# Parallel_CS_V5.net
KiCad netlist of a schematic drawn in EAGLE
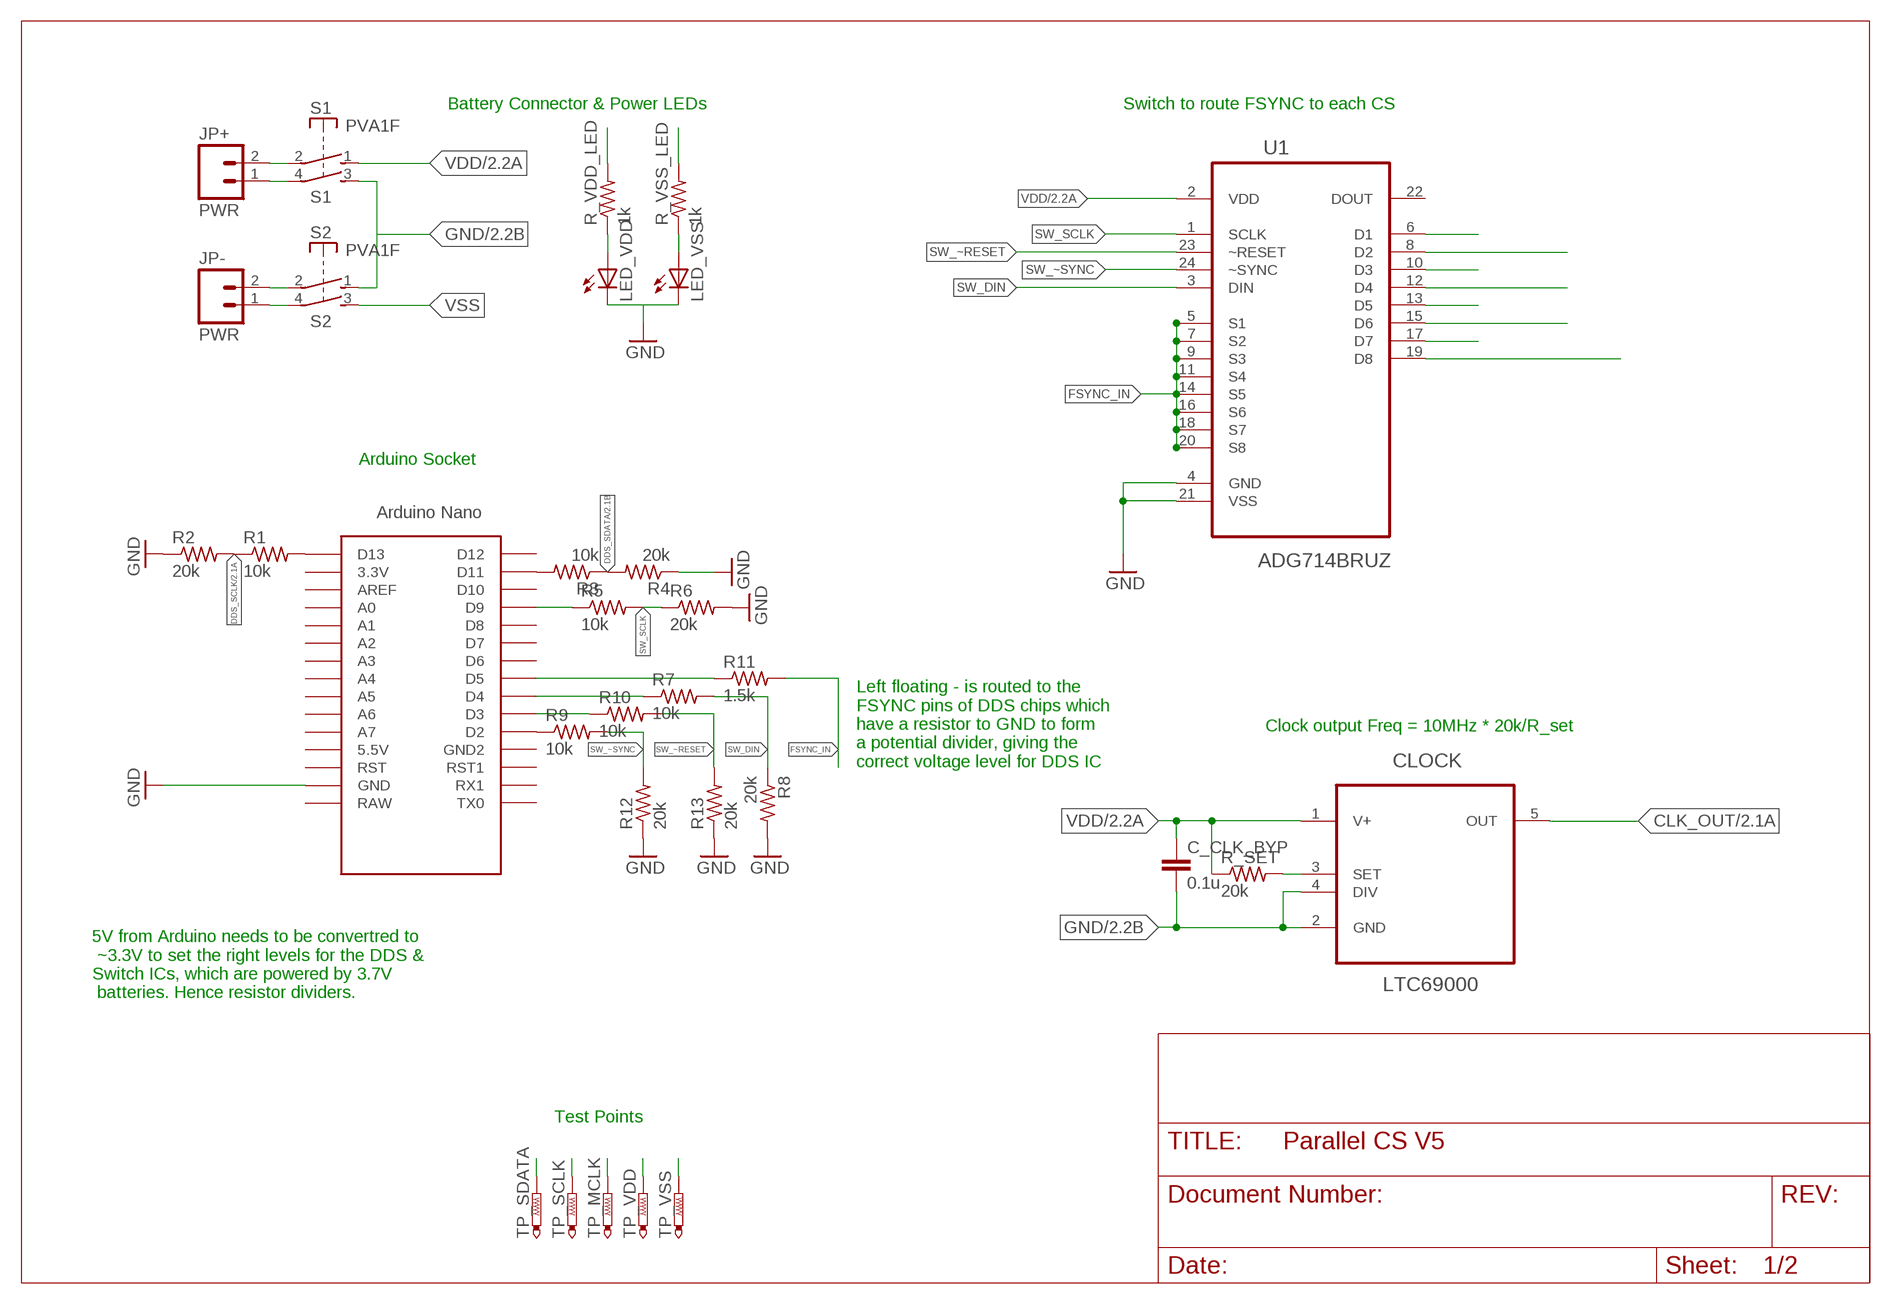
[diagram p0: schematic, sheet 1]
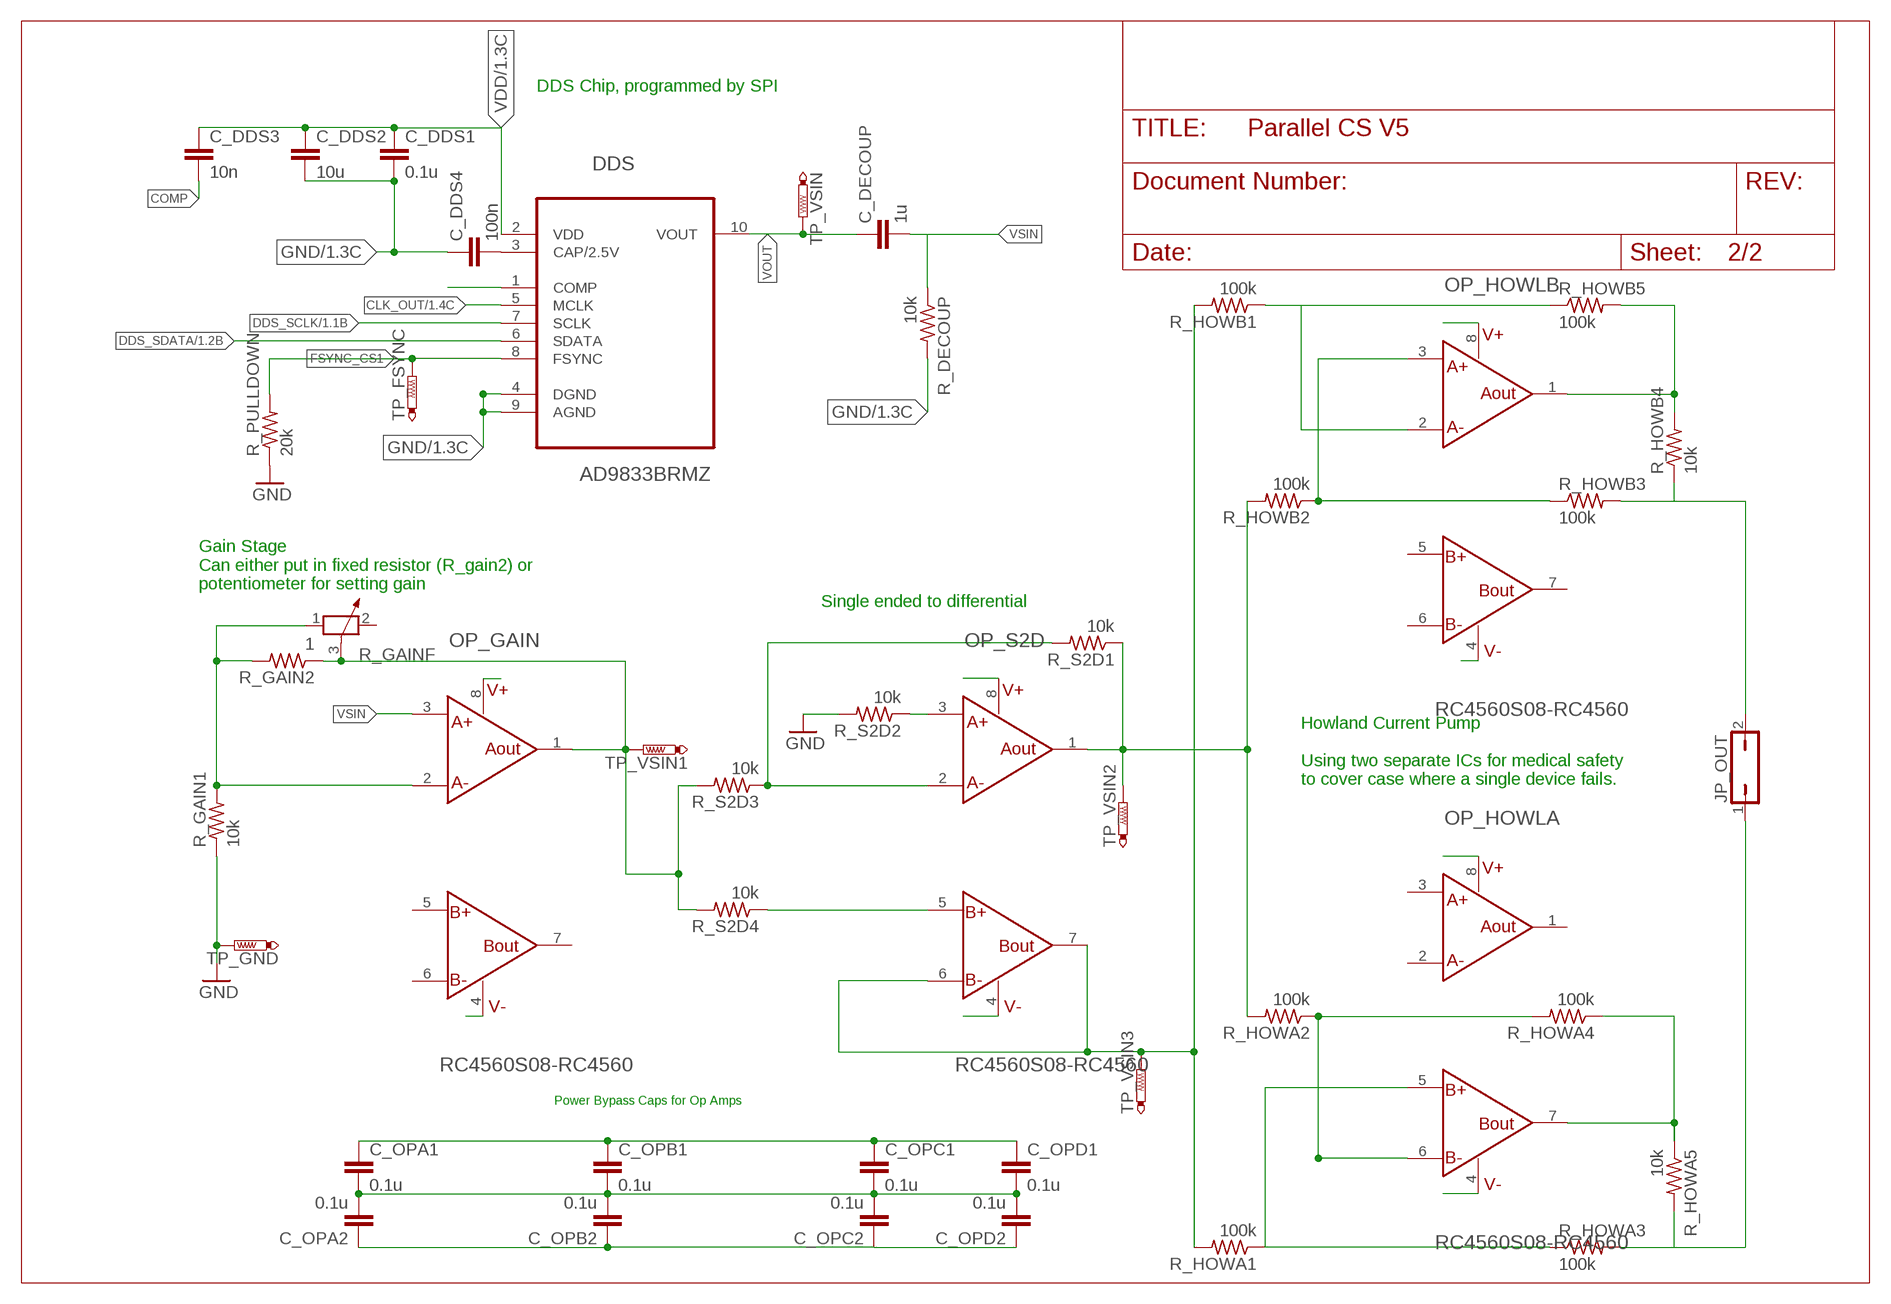
[diagram p1: schematic, sheet 2]

(export (version "E")
  (design (tool "Eeschema 10.0.6"))
  (components
    (comp (ref "CLOCK")
      (value "LTC69000")
      (footprint "eagle-import:SOT23-5L")
      (libsource (lib "eagle-import") (part "LTC69000"))
    )
    (comp (ref "C_CLK_BYP")
      (value "0.1u")
      (footprint "eagle-import:C0805")
      (libsource (lib "eagle-import") (part "C-EUC0805"))
    )
    (comp (ref "JP+")
      (value "PWR")
      (footprint "eagle-import:JST-2-SMD")
      (libsource (lib "eagle-import") (part "M02-JST-2MM-SMT"))
    )
    (comp (ref "JP-")
      (value "PWR")
      (footprint "eagle-import:JST-2-SMD")
      (libsource (lib "eagle-import") (part "M02-JST-2MM-SMT"))
    )
    (comp (ref "LED_VDD")
      (value "LEDSML0805")
      (footprint "eagle-import:SML0805")
      (libsource (lib "eagle-import") (part "LEDSML0805"))
    )
    (comp (ref "LED_VSS")
      (value "LEDSML0805")
      (footprint "eagle-import:SML0805")
      (libsource (lib "eagle-import") (part "LEDSML0805"))
    )
    (comp (ref "R1")
      (value "10k")
      (footprint "eagle-import:R0805")
      (libsource (lib "eagle-import") (part "resistor_R-US_R0805"))
    )
    (comp (ref "R2")
      (value "20k")
      (footprint "eagle-import:R0805")
      (libsource (lib "eagle-import") (part "resistor_R-US_R0805"))
    )
    (comp (ref "R3")
      (value "10k")
      (footprint "eagle-import:R0805")
      (libsource (lib "eagle-import") (part "resistor_R-US_R0805"))
    )
    (comp (ref "R4")
      (value "20k")
      (footprint "eagle-import:R0805")
      (libsource (lib "eagle-import") (part "resistor_R-US_R0805"))
    )
    (comp (ref "R5")
      (value "10k")
      (footprint "eagle-import:R0805")
      (libsource (lib "eagle-import") (part "resistor_R-US_R0805"))
    )
    (comp (ref "R6")
      (value "20k")
      (footprint "eagle-import:R0805")
      (libsource (lib "eagle-import") (part "resistor_R-US_R0805"))
    )
    (comp (ref "R7")
      (value "10k")
      (footprint "eagle-import:R0805")
      (libsource (lib "eagle-import") (part "resistor_R-US_R0805"))
    )
    (comp (ref "R8")
      (value "20k")
      (footprint "eagle-import:R0805")
      (libsource (lib "eagle-import") (part "resistor_R-US_R0805"))
    )
    (comp (ref "R9")
      (value "10k")
      (footprint "eagle-import:R0805")
      (libsource (lib "eagle-import") (part "resistor_R-US_R0805"))
    )
    (comp (ref "R10")
      (value "10k")
      (footprint "eagle-import:R0805")
      (libsource (lib "eagle-import") (part "resistor_R-US_R0805"))
    )
    (comp (ref "R11")
      (value "1.5k")
      (footprint "eagle-import:R0805")
      (libsource (lib "eagle-import") (part "resistor_R-US_R0805"))
    )
    (comp (ref "R12")
      (value "20k")
      (footprint "eagle-import:R0805")
      (libsource (lib "eagle-import") (part "resistor_R-US_R0805"))
    )
    (comp (ref "R13")
      (value "20k")
      (footprint "eagle-import:R0805")
      (libsource (lib "eagle-import") (part "resistor_R-US_R0805"))
    )
    (comp (ref "R_SET")
      (value "20k")
      (footprint "eagle-import:R0805")
      (libsource (lib "eagle-import") (part "resistor_R-US_R0805"))
    )
    (comp (ref "R_VDD_LED")
      (value "1k")
      (footprint "eagle-import:M0805")
      (libsource (lib "eagle-import") (part "resistor_R-US_M0805"))
    )
    (comp (ref "R_VSS_LED")
      (value "1k")
      (footprint "eagle-import:M0805")
      (libsource (lib "eagle-import") (part "resistor_R-US_M0805"))
    )
    (comp (ref "S1")
      (value "PVA1F")
      (footprint "eagle-import:PVA1F")
      (libsource (lib "eagle-import") (part "PVA1F"))
    )
    (comp (ref "S2")
      (value "PVA1F")
      (footprint "eagle-import:PVA1F")
      (libsource (lib "eagle-import") (part "PVA1F"))
    )
    (comp (ref "TP_MCLK")
      (value "PTR1PAD1-13")
      (footprint "eagle-import:P1-13")
      (libsource (lib "eagle-import") (part "PTR1PAD1-13"))
    )
    (comp (ref "TP_SCLK")
      (value "PTR1PAD1-13")
      (footprint "eagle-import:P1-13")
      (libsource (lib "eagle-import") (part "PTR1PAD1-13"))
    )
    (comp (ref "TP_SDATA")
      (value "PTR1PAD1-13")
      (footprint "eagle-import:P1-13")
      (libsource (lib "eagle-import") (part "PTR1PAD1-13"))
    )
    (comp (ref "TP_VDD")
      (value "PTR1PAD1-13")
      (footprint "eagle-import:P1-13")
      (libsource (lib "eagle-import") (part "PTR1PAD1-13"))
    )
    (comp (ref "TP_VSS")
      (value "PTR1PAD1-13")
      (footprint "eagle-import:P1-13")
      (libsource (lib "eagle-import") (part "PTR1PAD1-13"))
    )
    (comp (ref "U$1")
      (value "NANO")
      (footprint "eagle-import:NANO")
      (libsource (lib "eagle-import") (part "NANO"))
    )
    (comp (ref "U1")
      (value "ADG714BRUZ")
      (footprint "eagle-import:SOP65P640X120-24N")
      (libsource (lib "eagle-import") (part "ADG714BRUZ"))
    )
    (comp (ref "C_DDS1")
      (value "0.1u")
      (footprint "eagle-import:C0805")
      (libsource (lib "eagle-import") (part "C-EUC0805"))
    )
    (comp (ref "C_DDS2")
      (value "10u")
      (footprint "eagle-import:C0805")
      (libsource (lib "eagle-import") (part "C-EUC0805"))
    )
    (comp (ref "C_DDS3")
      (value "10n")
      (footprint "eagle-import:C0805")
      (libsource (lib "eagle-import") (part "C-EUC0805"))
    )
    (comp (ref "C_DDS4")
      (value "100n")
      (footprint "eagle-import:C0805")
      (libsource (lib "eagle-import") (part "C-EUC0805"))
    )
    (comp (ref "C_DECOUP")
      (value "1u")
      (footprint "eagle-import:C0805")
      (libsource (lib "eagle-import") (part "C-EUC0805"))
    )
    (comp (ref "C_OPA1")
      (value "0.1u")
      (footprint "eagle-import:C0805")
      (libsource (lib "eagle-import") (part "C-EUC0805"))
    )
    (comp (ref "C_OPA2")
      (value "0.1u")
      (footprint "eagle-import:C0805")
      (libsource (lib "eagle-import") (part "C-EUC0805"))
    )
    (comp (ref "C_OPB1")
      (value "0.1u")
      (footprint "eagle-import:C0805")
      (libsource (lib "eagle-import") (part "C-EUC0805"))
    )
    (comp (ref "C_OPB2")
      (value "0.1u")
      (footprint "eagle-import:C0805")
      (libsource (lib "eagle-import") (part "C-EUC0805"))
    )
    (comp (ref "C_OPC1")
      (value "0.1u")
      (footprint "eagle-import:C0805")
      (libsource (lib "eagle-import") (part "C-EUC0805"))
    )
    (comp (ref "C_OPC2")
      (value "0.1u")
      (footprint "eagle-import:C0805")
      (libsource (lib "eagle-import") (part "C-EUC0805"))
    )
    (comp (ref "C_OPD1")
      (value "0.1u")
      (footprint "eagle-import:C0805")
      (libsource (lib "eagle-import") (part "C-EUC0805"))
    )
    (comp (ref "C_OPD2")
      (value "0.1u")
      (footprint "eagle-import:C0805")
      (libsource (lib "eagle-import") (part "C-EUC0805"))
    )
    (comp (ref "DDS")
      (value "AD9833BRMZ")
      (footprint "eagle-import:SOP50P490X110-10N")
      (libsource (lib "eagle-import") (part "AD9833BRMZ"))
    )
    (comp (ref "JP_OUT")
      (value "JP1Q")
      (footprint "eagle-import:JP1")
      (libsource (lib "eagle-import") (part "JP1Q"))
    )
    (comp (ref "OP_GAIN")
      (value "RC4560S08-RC4560")
      (footprint "eagle-import:SO8")
      (libsource (lib "eagle-import") (part "RC4560S08-RC4560"))
    )
    (comp (ref "OP_HOWLA")
      (value "RC4560S08-RC4560")
      (footprint "eagle-import:SO8")
      (libsource (lib "eagle-import") (part "RC4560S08-RC4560"))
    )
    (comp (ref "OP_HOWLB")
      (value "RC4560S08-RC4560")
      (footprint "eagle-import:SO8")
      (libsource (lib "eagle-import") (part "RC4560S08-RC4560"))
    )
    (comp (ref "OP_S2D")
      (value "RC4560S08-RC4560")
      (footprint "eagle-import:SO8")
      (libsource (lib "eagle-import") (part "RC4560S08-RC4560"))
    )
    (comp (ref "R_DECOUP")
      (value "10k")
      (footprint "eagle-import:R0805")
      (libsource (lib "eagle-import") (part "R-US_R0805"))
    )
    (comp (ref "R_GAIN1")
      (value "10k")
      (footprint "eagle-import:R0805")
      (libsource (lib "eagle-import") (part "R-US_R0805"))
    )
    (comp (ref "R_GAIN2")
      (value "1")
      (footprint "eagle-import:R0805")
      (libsource (lib "eagle-import") (part "R-US_R0805"))
    )
    (comp (ref "R_GAINF")
      (value "POTENTIOMETER_PT-10")
      (footprint "eagle-import:PT-10")
      (libsource (lib "eagle-import") (part "POTENTIOMETER_PT-10"))
    )
    (comp (ref "R_HOWA1")
      (value "100k")
      (footprint "eagle-import:R0805")
      (libsource (lib "eagle-import") (part "R-US_R0805"))
    )
    (comp (ref "R_HOWA2")
      (value "100k")
      (footprint "eagle-import:R0805")
      (libsource (lib "eagle-import") (part "R-US_R0805"))
    )
    (comp (ref "R_HOWA3")
      (value "100k")
      (footprint "eagle-import:R0805")
      (libsource (lib "eagle-import") (part "R-US_R0805"))
    )
    (comp (ref "R_HOWA4")
      (value "100k")
      (footprint "eagle-import:R0805")
      (libsource (lib "eagle-import") (part "R-US_R0805"))
    )
    (comp (ref "R_HOWA5")
      (value "10k")
      (footprint "eagle-import:R0805")
      (libsource (lib "eagle-import") (part "R-US_R0805"))
    )
    (comp (ref "R_HOWB1")
      (value "100k")
      (footprint "eagle-import:R0805")
      (libsource (lib "eagle-import") (part "R-US_R0805"))
    )
    (comp (ref "R_HOWB2")
      (value "100k")
      (footprint "eagle-import:R0805")
      (libsource (lib "eagle-import") (part "R-US_R0805"))
    )
    (comp (ref "R_HOWB3")
      (value "100k")
      (footprint "eagle-import:R0805")
      (libsource (lib "eagle-import") (part "R-US_R0805"))
    )
    (comp (ref "R_HOWB4")
      (value "10k")
      (footprint "eagle-import:R0805")
      (libsource (lib "eagle-import") (part "R-US_R0805"))
    )
    (comp (ref "R_HOWB5")
      (value "100k")
      (footprint "eagle-import:R0805")
      (libsource (lib "eagle-import") (part "R-US_R0805"))
    )
    (comp (ref "R_PULLDOWN")
      (value "20k")
      (footprint "eagle-import:R0805")
      (libsource (lib "eagle-import") (part "R-US_R0805"))
    )
    (comp (ref "R_S2D1")
      (value "10k")
      (footprint "eagle-import:R0805")
      (libsource (lib "eagle-import") (part "R-US_R0805"))
    )
    (comp (ref "R_S2D2")
      (value "10k")
      (footprint "eagle-import:R0805")
      (libsource (lib "eagle-import") (part "R-US_R0805"))
    )
    (comp (ref "R_S2D3")
      (value "10k")
      (footprint "eagle-import:R0805")
      (libsource (lib "eagle-import") (part "R-US_R0805"))
    )
    (comp (ref "R_S2D4")
      (value "10k")
      (footprint "eagle-import:R0805")
      (libsource (lib "eagle-import") (part "R-US_R0805"))
    )
    (comp (ref "TP_FSYNC")
      (value "PTR1PAD1-13")
      (footprint "eagle-import:P1-13")
      (libsource (lib "eagle-import") (part "PTR1PAD1-13"))
    )
    (comp (ref "TP_GND")
      (value "PTR1PAD1-13")
      (footprint "eagle-import:P1-13")
      (libsource (lib "eagle-import") (part "PTR1PAD1-13"))
    )
    (comp (ref "TP_VSIN")
      (value "PTR1PAD1-13")
      (footprint "eagle-import:P1-13")
      (libsource (lib "eagle-import") (part "PTR1PAD1-13"))
    )
    (comp (ref "TP_VSIN1")
      (value "PTR1PAD1-13")
      (footprint "eagle-import:P1-13")
      (libsource (lib "eagle-import") (part "PTR1PAD1-13"))
    )
    (comp (ref "TP_VSIN2")
      (value "PTR1PAD1-13")
      (footprint "eagle-import:P1-13")
      (libsource (lib "eagle-import") (part "PTR1PAD1-13"))
    )
    (comp (ref "TP_VSIN3")
      (value "PTR1PAD1-13")
      (footprint "eagle-import:P1-13")
      (libsource (lib "eagle-import") (part "PTR1PAD1-13"))
    )
  )
  (nets
    (net (code "1") (name "CLK_OUT") (class "Default")
      (node (ref "CLOCK") (pin "5") (pinfunction "OUT_5") (pintype "output"))
      (node (ref "DDS") (pin "5") (pinfunction "MCLK_5") (pintype "input"))
      (node (ref "TP_MCLK") (pin "TP") (pinfunction "TP_TP") (pintype "input"))
    )
    (net (code "2") (name "COMP") (class "Default")
      (node (ref "C_DDS3") (pin "2") (pinfunction "2_2") (pintype "passive"))
      (node (ref "DDS") (pin "1") (pinfunction "COMP_1") (pintype "passive"))
    )
    (net (code "3") (name "DDS_SCLK") (class "Default")
      (node (ref "DDS") (pin "7") (pinfunction "SCLK_7") (pintype "input"))
      (node (ref "R1") (pin "1") (pinfunction "1_1") (pintype "passive"))
      (node (ref "R2") (pin "2") (pinfunction "2_2") (pintype "passive"))
      (node (ref "TP_SCLK") (pin "TP") (pinfunction "TP_TP") (pintype "input"))
    )
    (net (code "4") (name "DDS_SDATA") (class "Default")
      (node (ref "DDS") (pin "6") (pinfunction "SDATA_6") (pintype "input"))
      (node (ref "R3") (pin "1") (pinfunction "1_1") (pintype "passive"))
      (node (ref "R4") (pin "2") (pinfunction "2_2") (pintype "passive"))
      (node (ref "TP_SDATA") (pin "TP") (pinfunction "TP_TP") (pintype "input"))
    )
    (net (code "5") (name "FSYNC_CS1") (class "Default")
      (node (ref "DDS") (pin "8") (pinfunction "FSYNC_8") (pintype "input"))
      (node (ref "R_PULLDOWN") (pin "2") (pinfunction "2_2") (pintype "passive"))
      (node (ref "TP_FSYNC") (pin "TP") (pinfunction "TP_TP") (pintype "input"))
      (node (ref "U1") (pin "6") (pinfunction "D1_6") (pintype "bidirectional"))
    )
    (net (code "6") (name "FSYNC_IN") (class "Default")
      (node (ref "R11") (pin "2") (pinfunction "2_2") (pintype "passive"))
      (node (ref "U1") (pin "11") (pinfunction "S4_11") (pintype "bidirectional"))
      (node (ref "U1") (pin "14") (pinfunction "S5_14") (pintype "bidirectional"))
      (node (ref "U1") (pin "16") (pinfunction "S6_16") (pintype "bidirectional"))
      (node (ref "U1") (pin "18") (pinfunction "S7_18") (pintype "bidirectional"))
      (node (ref "U1") (pin "20") (pinfunction "S8_20") (pintype "bidirectional"))
      (node (ref "U1") (pin "5") (pinfunction "S1_5") (pintype "bidirectional"))
      (node (ref "U1") (pin "7") (pinfunction "S2_7") (pintype "bidirectional"))
      (node (ref "U1") (pin "9") (pinfunction "S3_9") (pintype "bidirectional"))
    )
    (net (code "7") (name "GND") (class "Default")
      (node (ref "CLOCK") (pin "2") (pinfunction "GND_2") (pintype "passive"))
      (node (ref "CLOCK") (pin "4") (pinfunction "DIV_4") (pintype "input"))
      (node (ref "C_CLK_BYP") (pin "2") (pinfunction "2_2") (pintype "passive"))
      (node (ref "C_DDS1") (pin "2") (pinfunction "2_2") (pintype "passive"))
      (node (ref "C_DDS2") (pin "2") (pinfunction "2_2") (pintype "passive"))
      (node (ref "C_DDS4") (pin "1") (pinfunction "1_1") (pintype "passive"))
      (node (ref "C_OPA1") (pin "2") (pinfunction "2_2") (pintype "passive"))
      (node (ref "C_OPA2") (pin "2") (pinfunction "2_2") (pintype "passive"))
      (node (ref "C_OPB1") (pin "2") (pinfunction "2_2") (pintype "passive"))
      (node (ref "C_OPB2") (pin "2") (pinfunction "2_2") (pintype "passive"))
      (node (ref "C_OPC1") (pin "2") (pinfunction "2_2") (pintype "passive"))
      (node (ref "C_OPC2") (pin "2") (pinfunction "2_2") (pintype "passive"))
      (node (ref "C_OPD1") (pin "2") (pinfunction "2_2") (pintype "passive"))
      (node (ref "C_OPD2") (pin "2") (pinfunction "2_2") (pintype "passive"))
      (node (ref "DDS") (pin "4") (pinfunction "DGND_4") (pintype "passive"))
      (node (ref "DDS") (pin "9") (pinfunction "AGND_9") (pintype "passive"))
      (node (ref "LED_VDD") (pin "C") (pinfunction "C_C") (pintype "passive"))
      (node (ref "LED_VSS") (pin "C") (pinfunction "C_C") (pintype "passive"))
      (node (ref "R12") (pin "1") (pinfunction "1_1") (pintype "passive"))
      (node (ref "R13") (pin "1") (pinfunction "1_1") (pintype "passive"))
      (node (ref "R2") (pin "1") (pinfunction "1_1") (pintype "passive"))
      (node (ref "R4") (pin "1") (pinfunction "1_1") (pintype "passive"))
      (node (ref "R6") (pin "2") (pinfunction "2_2") (pintype "passive"))
      (node (ref "R8") (pin "2") (pinfunction "2_2") (pintype "passive"))
      (node (ref "R_DECOUP") (pin "2") (pinfunction "2_2") (pintype "passive"))
      (node (ref "R_GAIN1") (pin "1") (pinfunction "1_1") (pintype "passive"))
      (node (ref "R_PULLDOWN") (pin "1") (pinfunction "1_1") (pintype "passive"))
      (node (ref "R_S2D2") (pin "2") (pinfunction "2_2") (pintype "passive"))
      (node (ref "S1") (pin "3") (pinfunction "S_3") (pintype "passive"))
      (node (ref "S2") (pin "1") (pinfunction "S_1") (pintype "passive"))
      (node (ref "TP_GND") (pin "TP") (pinfunction "TP_TP") (pintype "input"))
      (node (ref "U$1") (pin "GND") (pinfunction "GND_GND") (pintype "bidirectional"))
      (node (ref "U1") (pin "21") (pinfunction "VSS_21") (pintype "power_in"))
      (node (ref "U1") (pin "4") (pinfunction "GND_4") (pintype "passive"))
    )
    (net (code "8") (name "Net-(CLOCK-SET)") (class "Default")
      (node (ref "CLOCK") (pin "3") (pinfunction "SET_3") (pintype "input"))
      (node (ref "R_SET") (pin "2") (pinfunction "2_2") (pintype "passive"))
    )
    (net (code "9") (name "Net-(DDS-CAP{slash}2.5V)") (class "Default")
      (node (ref "C_DDS4") (pin "2") (pinfunction "2_2") (pintype "passive"))
      (node (ref "DDS") (pin "3") (pinfunction "CAP/2.5V_3") (pintype "passive"))
    )
    (net (code "10") (name "Net-(JP_OUT-Pad1)") (class "Default")
      (node (ref "JP_OUT") (pin "1") (pinfunction "1_1") (pintype "passive"))
      (node (ref "R_HOWA3") (pin "2") (pinfunction "2_2") (pintype "passive"))
      (node (ref "R_HOWA5") (pin "2") (pinfunction "2_2") (pintype "passive"))
    )
    (net (code "11") (name "Net-(JP_OUT-Pad2)") (class "Default")
      (node (ref "JP_OUT") (pin "2") (pinfunction "2_2") (pintype "passive"))
      (node (ref "R_HOWB3") (pin "2") (pinfunction "2_2") (pintype "passive"))
      (node (ref "R_HOWB4") (pin "1") (pinfunction "1_1") (pintype "passive"))
    )
    (net (code "12") (name "Net-(LED_VDD-PadA)") (class "Default")
      (node (ref "LED_VDD") (pin "A") (pinfunction "A_A") (pintype "passive"))
      (node (ref "R_VDD_LED") (pin "1") (pinfunction "1_1") (pintype "passive"))
    )
    (net (code "13") (name "Net-(LED_VSS-PadA)") (class "Default")
      (node (ref "LED_VSS") (pin "A") (pinfunction "A_A") (pintype "passive"))
      (node (ref "R_VSS_LED") (pin "1") (pinfunction "1_1") (pintype "passive"))
    )
    (net (code "14") (name "Net-(OP_GAIN-NEGA)") (class "Default")
      (node (ref "OP_GAIN") (pin "2") (pinfunction "NEGA_2") (pintype "input"))
      (node (ref "R_GAIN1") (pin "2") (pinfunction "2_2") (pintype "passive"))
      (node (ref "R_GAIN2") (pin "2") (pinfunction "2_2") (pintype "passive"))
      (node (ref "R_GAINF") (pin "1") (pinfunction "1_1") (pintype "passive"))
    )
    (net (code "15") (name "Net-(OP_GAIN-OUTA)") (class "Default")
      (node (ref "OP_GAIN") (pin "1") (pinfunction "OUTA_1") (pintype "output"))
      (node (ref "R_GAIN2") (pin "1") (pinfunction "1_1") (pintype "passive"))
      (node (ref "R_GAINF") (pin "3") (pinfunction "3_3") (pintype "passive"))
      (node (ref "R_S2D3") (pin "2") (pinfunction "2_2") (pintype "passive"))
      (node (ref "R_S2D4") (pin "2") (pinfunction "2_2") (pintype "passive"))
      (node (ref "TP_VSIN1") (pin "TP") (pinfunction "TP_TP") (pintype "input"))
    )
    (net (code "16") (name "Net-(OP_HOWLA-NEGB)") (class "Default")
      (node (ref "OP_HOWLA") (pin "6") (pinfunction "NEGB_6") (pintype "input"))
      (node (ref "R_HOWA2") (pin "1") (pinfunction "1_1") (pintype "passive"))
      (node (ref "R_HOWA4") (pin "2") (pinfunction "2_2") (pintype "passive"))
    )
    (net (code "17") (name "Net-(OP_HOWLA-OUTB)") (class "Default")
      (node (ref "OP_HOWLA") (pin "7") (pinfunction "OUTB_7") (pintype "output"))
      (node (ref "R_HOWA4") (pin "1") (pinfunction "1_1") (pintype "passive"))
      (node (ref "R_HOWA5") (pin "1") (pinfunction "1_1") (pintype "passive"))
    )
    (net (code "18") (name "Net-(OP_HOWLA-POSB)") (class "Default")
      (node (ref "OP_HOWLA") (pin "5") (pinfunction "POSB_5") (pintype "input"))
      (node (ref "R_HOWA1") (pin "1") (pinfunction "1_1") (pintype "passive"))
      (node (ref "R_HOWA3") (pin "1") (pinfunction "1_1") (pintype "passive"))
    )
    (net (code "19") (name "Net-(OP_HOWLB-NEGA)") (class "Default")
      (node (ref "OP_HOWLB") (pin "2") (pinfunction "NEGA_2") (pintype "input"))
      (node (ref "R_HOWB1") (pin "1") (pinfunction "1_1") (pintype "passive"))
      (node (ref "R_HOWB5") (pin "1") (pinfunction "1_1") (pintype "passive"))
    )
    (net (code "20") (name "Net-(OP_HOWLB-OUTA)") (class "Default")
      (node (ref "OP_HOWLB") (pin "1") (pinfunction "OUTA_1") (pintype "output"))
      (node (ref "R_HOWB4") (pin "2") (pinfunction "2_2") (pintype "passive"))
      (node (ref "R_HOWB5") (pin "2") (pinfunction "2_2") (pintype "passive"))
    )
    (net (code "21") (name "Net-(OP_HOWLB-POSA)") (class "Default")
      (node (ref "OP_HOWLB") (pin "3") (pinfunction "POSA_3") (pintype "input"))
      (node (ref "R_HOWB2") (pin "1") (pinfunction "1_1") (pintype "passive"))
      (node (ref "R_HOWB3") (pin "1") (pinfunction "1_1") (pintype "passive"))
    )
    (net (code "22") (name "Net-(OP_S2D-NEGA)") (class "Default")
      (node (ref "OP_S2D") (pin "2") (pinfunction "NEGA_2") (pintype "input"))
      (node (ref "R_S2D1") (pin "2") (pinfunction "2_2") (pintype "passive"))
      (node (ref "R_S2D3") (pin "1") (pinfunction "1_1") (pintype "passive"))
    )
    (net (code "23") (name "Net-(OP_S2D-NEGB)") (class "Default")
      (node (ref "OP_S2D") (pin "6") (pinfunction "NEGB_6") (pintype "input"))
      (node (ref "OP_S2D") (pin "7") (pinfunction "OUTB_7") (pintype "output"))
      (node (ref "R_HOWA1") (pin "2") (pinfunction "2_2") (pintype "passive"))
      (node (ref "R_HOWB1") (pin "2") (pinfunction "2_2") (pintype "passive"))
      (node (ref "TP_VSIN3") (pin "TP") (pinfunction "TP_TP") (pintype "input"))
    )
    (net (code "24") (name "Net-(OP_S2D-OUTA)") (class "Default")
      (node (ref "OP_S2D") (pin "1") (pinfunction "OUTA_1") (pintype "output"))
      (node (ref "R_HOWA2") (pin "2") (pinfunction "2_2") (pintype "passive"))
      (node (ref "R_HOWB2") (pin "2") (pinfunction "2_2") (pintype "passive"))
      (node (ref "R_S2D1") (pin "1") (pinfunction "1_1") (pintype "passive"))
      (node (ref "TP_VSIN2") (pin "TP") (pinfunction "TP_TP") (pintype "input"))
    )
    (net (code "25") (name "Net-(OP_S2D-POSA)") (class "Default")
      (node (ref "OP_S2D") (pin "3") (pinfunction "POSA_3") (pintype "input"))
      (node (ref "R_S2D2") (pin "1") (pinfunction "1_1") (pintype "passive"))
    )
    (net (code "26") (name "Net-(OP_S2D-POSB)") (class "Default")
      (node (ref "OP_S2D") (pin "5") (pinfunction "POSB_5") (pintype "input"))
      (node (ref "R_S2D4") (pin "1") (pinfunction "1_1") (pintype "passive"))
    )
    (net (code "27") (name "Net-(R1-Pad2)") (class "Default")
      (node (ref "R1") (pin "2") (pinfunction "2_2") (pintype "passive"))
      (node (ref "U$1") (pin "D13") (pinfunction "D13_D13") (pintype "bidirectional"))
    )
    (net (code "28") (name "Net-(R3-Pad2)") (class "Default")
      (node (ref "R3") (pin "2") (pinfunction "2_2") (pintype "passive"))
      (node (ref "U$1") (pin "D11") (pinfunction "D11_D11") (pintype "bidirectional"))
    )
    (net (code "29") (name "Net-(R5-Pad1)") (class "Default")
      (node (ref "R5") (pin "1") (pinfunction "1_1") (pintype "passive"))
      (node (ref "U$1") (pin "D9") (pinfunction "D9_D9") (pintype "bidirectional"))
    )
    (net (code "30") (name "Net-(R7-Pad1)") (class "Default")
      (node (ref "R7") (pin "1") (pinfunction "1_1") (pintype "passive"))
      (node (ref "U$1") (pin "D4") (pinfunction "D4_D4") (pintype "bidirectional"))
    )
    (net (code "31") (name "Net-(R9-Pad1)") (class "Default")
      (node (ref "R9") (pin "1") (pinfunction "1_1") (pintype "passive"))
      (node (ref "U$1") (pin "D2") (pinfunction "D2_D2") (pintype "bidirectional"))
    )
    (net (code "32") (name "Net-(R10-Pad1)") (class "Default")
      (node (ref "R10") (pin "1") (pinfunction "1_1") (pintype "passive"))
      (node (ref "U$1") (pin "D3") (pinfunction "D3_D3") (pintype "bidirectional"))
    )
    (net (code "33") (name "Net-(R11-Pad1)") (class "Default")
      (node (ref "R11") (pin "1") (pinfunction "1_1") (pintype "passive"))
      (node (ref "U$1") (pin "D5") (pinfunction "D5_D5") (pintype "bidirectional"))
    )
    (net (code "34") (name "Net-(S1A-P)") (class "Default")
      (node (ref "JP+") (pin "2") (pinfunction "2_2") (pintype "passive"))
      (node (ref "S1") (pin "2") (pinfunction "P_2") (pintype "passive"))
    )
    (net (code "35") (name "Net-(S1B-P)") (class "Default")
      (node (ref "JP+") (pin "1") (pinfunction "1_1") (pintype "passive"))
      (node (ref "S1") (pin "4") (pinfunction "P_4") (pintype "passive"))
    )
    (net (code "36") (name "Net-(S2A-P)") (class "Default")
      (node (ref "JP-") (pin "2") (pinfunction "2_2") (pintype "passive"))
      (node (ref "S2") (pin "2") (pinfunction "P_2") (pintype "passive"))
    )
    (net (code "37") (name "Net-(S2B-P)") (class "Default")
      (node (ref "JP-") (pin "1") (pinfunction "1_1") (pintype "passive"))
      (node (ref "S2") (pin "4") (pinfunction "P_4") (pintype "passive"))
    )
    (net (code "38") (name "SW_DIN") (class "Default")
      (node (ref "R7") (pin "2") (pinfunction "2_2") (pintype "passive"))
      (node (ref "R8") (pin "1") (pinfunction "1_1") (pintype "passive"))
      (node (ref "U1") (pin "3") (pinfunction "DIN_3") (pintype "input"))
    )
    (net (code "39") (name "SW_SCLK") (class "Default")
      (node (ref "R5") (pin "2") (pinfunction "2_2") (pintype "passive"))
      (node (ref "R6") (pin "1") (pinfunction "1_1") (pintype "passive"))
      (node (ref "U1") (pin "1") (pinfunction "SCLK_1") (pintype "input"))
    )
    (net (code "40") (name "SW_~{RESET}") (class "Default")
      (node (ref "R10") (pin "2") (pinfunction "2_2") (pintype "passive"))
      (node (ref "R13") (pin "2") (pinfunction "2_2") (pintype "passive"))
      (node (ref "U1") (pin "23") (pinfunction "~{RESET}_23") (pintype "input"))
    )
    (net (code "41") (name "SW_~{SYNC}") (class "Default")
      (node (ref "R12") (pin "2") (pinfunction "2_2") (pintype "passive"))
      (node (ref "R9") (pin "2") (pinfunction "2_2") (pintype "passive"))
      (node (ref "U1") (pin "24") (pinfunction "~{SYNC}_24") (pintype "input"))
    )
    (net (code "42") (name "VDD") (class "Default")
      (node (ref "CLOCK") (pin "1") (pinfunction "V+_1") (pintype "power_in"))
      (node (ref "C_CLK_BYP") (pin "1") (pinfunction "1_1") (pintype "passive"))
      (node (ref "C_DDS1") (pin "1") (pinfunction "1_1") (pintype "passive"))
      (node (ref "C_DDS2") (pin "1") (pinfunction "1_1") (pintype "passive"))
      (node (ref "C_DDS3") (pin "1") (pinfunction "1_1") (pintype "passive"))
      (node (ref "C_OPA1") (pin "1") (pinfunction "1_1") (pintype "passive"))
      (node (ref "C_OPB1") (pin "1") (pinfunction "1_1") (pintype "passive"))
      (node (ref "C_OPC1") (pin "1") (pinfunction "1_1") (pintype "passive"))
      (node (ref "C_OPD1") (pin "1") (pinfunction "1_1") (pintype "passive"))
      (node (ref "DDS") (pin "2") (pinfunction "VDD_2") (pintype "power_in"))
      (node (ref "OP_GAIN") (pin "8") (pinfunction "V+_8") (pintype "power_in"))
      (node (ref "OP_HOWLA") (pin "8") (pinfunction "V+_8") (pintype "power_in"))
      (node (ref "OP_HOWLB") (pin "8") (pinfunction "V+_8") (pintype "power_in"))
      (node (ref "OP_S2D") (pin "8") (pinfunction "V+_8") (pintype "power_in"))
      (node (ref "R_SET") (pin "1") (pinfunction "1_1") (pintype "passive"))
      (node (ref "R_VDD_LED") (pin "2") (pinfunction "2_2") (pintype "passive"))
      (node (ref "S1") (pin "1") (pinfunction "S_1") (pintype "passive"))
      (node (ref "TP_VDD") (pin "TP") (pinfunction "TP_TP") (pintype "input"))
      (node (ref "U1") (pin "2") (pinfunction "VDD_2") (pintype "power_in"))
    )
    (net (code "43") (name "VOUT") (class "Default")
      (node (ref "C_DECOUP") (pin "1") (pinfunction "1_1") (pintype "passive"))
      (node (ref "DDS") (pin "10") (pinfunction "VOUT_10") (pintype "output"))
      (node (ref "TP_VSIN") (pin "TP") (pinfunction "TP_TP") (pintype "input"))
    )
    (net (code "44") (name "VSIN") (class "Default")
      (node (ref "C_DECOUP") (pin "2") (pinfunction "2_2") (pintype "passive"))
      (node (ref "OP_GAIN") (pin "3") (pinfunction "POSA_3") (pintype "input"))
      (node (ref "R_DECOUP") (pin "1") (pinfunction "1_1") (pintype "passive"))
    )
    (net (code "45") (name "VSS") (class "Default")
      (node (ref "C_OPA2") (pin "1") (pinfunction "1_1") (pintype "passive"))
      (node (ref "C_OPB2") (pin "1") (pinfunction "1_1") (pintype "passive"))
      (node (ref "C_OPC2") (pin "1") (pinfunction "1_1") (pintype "passive"))
      (node (ref "C_OPD2") (pin "1") (pinfunction "1_1") (pintype "passive"))
      (node (ref "OP_GAIN") (pin "4") (pinfunction "V-_4") (pintype "power_in"))
      (node (ref "OP_HOWLA") (pin "4") (pinfunction "V-_4") (pintype "power_in"))
      (node (ref "OP_HOWLB") (pin "4") (pinfunction "V-_4") (pintype "power_in"))
      (node (ref "OP_S2D") (pin "4") (pinfunction "V-_4") (pintype "power_in"))
      (node (ref "R_VSS_LED") (pin "2") (pinfunction "2_2") (pintype "passive"))
      (node (ref "S2") (pin "3") (pinfunction "S_3") (pintype "passive"))
      (node (ref "TP_VSS") (pin "TP") (pinfunction "TP_TP") (pintype "input"))
    )
    (net (code "46") (name "unconnected-(OP_GAIN-NEGB-Pad6)") (class "Default")
      (node (ref "OP_GAIN") (pin "6") (pinfunction "NEGB_6") (pintype "input"))
    )
    (net (code "47") (name "unconnected-(OP_GAIN-OUTB-Pad7)") (class "Default")
      (node (ref "OP_GAIN") (pin "7") (pinfunction "OUTB_7") (pintype "output"))
    )
    (net (code "48") (name "unconnected-(OP_GAIN-POSB-Pad5)") (class "Default")
      (node (ref "OP_GAIN") (pin "5") (pinfunction "POSB_5") (pintype "input"))
    )
    (net (code "49") (name "unconnected-(OP_HOWLA-NEGA-Pad2)") (class "Default")
      (node (ref "OP_HOWLA") (pin "2") (pinfunction "NEGA_2") (pintype "input"))
    )
    (net (code "50") (name "unconnected-(OP_HOWLA-OUTA-Pad1)") (class "Default")
      (node (ref "OP_HOWLA") (pin "1") (pinfunction "OUTA_1") (pintype "output"))
    )
    (net (code "51") (name "unconnected-(OP_HOWLA-POSA-Pad3)") (class "Default")
      (node (ref "OP_HOWLA") (pin "3") (pinfunction "POSA_3") (pintype "input"))
    )
    (net (code "52") (name "unconnected-(OP_HOWLB-NEGB-Pad6)") (class "Default")
      (node (ref "OP_HOWLB") (pin "6") (pinfunction "NEGB_6") (pintype "input"))
    )
    (net (code "53") (name "unconnected-(OP_HOWLB-OUTB-Pad7)") (class "Default")
      (node (ref "OP_HOWLB") (pin "7") (pinfunction "OUTB_7") (pintype "output"))
    )
    (net (code "54") (name "unconnected-(OP_HOWLB-POSB-Pad5)") (class "Default")
      (node (ref "OP_HOWLB") (pin "5") (pinfunction "POSB_5") (pintype "input"))
    )
    (net (code "55") (name "unconnected-(R_GAINF-Pad2)") (class "Default")
      (node (ref "R_GAINF") (pin "2") (pinfunction "2_2") (pintype "passive"))
    )
    (net (code "56") (name "unconnected-(U$1-5.5V-Pad5V)") (class "Default")
      (node (ref "U$1") (pin "5V") (pinfunction "5.5V_5V") (pintype "bidirectional"))
    )
    (net (code "57") (name "unconnected-(U$1-GND2-PadGND1)") (class "Default")
      (node (ref "U$1") (pin "GND1") (pinfunction "GND2_GND1") (pintype "bidirectional"))
    )
    (net (code "58") (name "unconnected-(U$1-Pad3.3V)") (class "Default")
      (node (ref "U$1") (pin "3.3V") (pinfunction "3.3V_3.3V") (pintype "bidirectional"))
    )
    (net (code "59") (name "unconnected-(U$1-PadA0)") (class "Default")
      (node (ref "U$1") (pin "A0") (pinfunction "A0_A0") (pintype "bidirectional"))
    )
    (net (code "60") (name "unconnected-(U$1-PadA1)") (class "Default")
      (node (ref "U$1") (pin "A1") (pinfunction "A1_A1") (pintype "bidirectional"))
    )
    (net (code "61") (name "unconnected-(U$1-PadA2)") (class "Default")
      (node (ref "U$1") (pin "A2") (pinfunction "A2_A2") (pintype "bidirectional"))
    )
    (net (code "62") (name "unconnected-(U$1-PadA3)") (class "Default")
      (node (ref "U$1") (pin "A3") (pinfunction "A3_A3") (pintype "bidirectional"))
    )
    (net (code "63") (name "unconnected-(U$1-PadA4)") (class "Default")
      (node (ref "U$1") (pin "A4") (pinfunction "A4_A4") (pintype "bidirectional"))
    )
    (net (code "64") (name "unconnected-(U$1-PadA5)") (class "Default")
      (node (ref "U$1") (pin "A5") (pinfunction "A5_A5") (pintype "bidirectional"))
    )
    (net (code "65") (name "unconnected-(U$1-PadA6)") (class "Default")
      (node (ref "U$1") (pin "A6") (pinfunction "A6_A6") (pintype "bidirectional"))
    )
    (net (code "66") (name "unconnected-(U$1-PadA7)") (class "Default")
      (node (ref "U$1") (pin "A7") (pinfunction "A7_A7") (pintype "bidirectional"))
    )
    (net (code "67") (name "unconnected-(U$1-PadAREF)") (class "Default")
      (node (ref "U$1") (pin "AREF") (pinfunction "AREF_AREF") (pintype "bidirectional"))
    )
    (net (code "68") (name "unconnected-(U$1-PadD6)") (class "Default")
      (node (ref "U$1") (pin "D6") (pinfunction "D6_D6") (pintype "bidirectional"))
    )
    (net (code "69") (name "unconnected-(U$1-PadD7)") (class "Default")
      (node (ref "U$1") (pin "D7") (pinfunction "D7_D7") (pintype "bidirectional"))
    )
    (net (code "70") (name "unconnected-(U$1-PadD8)") (class "Default")
      (node (ref "U$1") (pin "D8") (pinfunction "D8_D8") (pintype "bidirectional"))
    )
    (net (code "71") (name "unconnected-(U$1-PadD10)") (class "Default")
      (node (ref "U$1") (pin "D10") (pinfunction "D10_D10") (pintype "bidirectional"))
    )
    (net (code "72") (name "unconnected-(U$1-PadD12)") (class "Default")
      (node (ref "U$1") (pin "D12") (pinfunction "D12_D12") (pintype "bidirectional"))
    )
    (net (code "73") (name "unconnected-(U$1-PadICSP1)") (class "Default")
      (node (ref "U$1") (pin "ICSP1") (pinfunction "ICSP1_ICSP1") (pintype "bidirectional"))
    )
    (net (code "74") (name "unconnected-(U$1-PadICSP2)") (class "Default")
      (node (ref "U$1") (pin "ICSP2") (pinfunction "ICSP2_ICSP2") (pintype "bidirectional"))
    )
    (net (code "75") (name "unconnected-(U$1-PadICSP3)") (class "Default")
      (node (ref "U$1") (pin "ICSP3") (pinfunction "ICSP3_ICSP3") (pintype "bidirectional"))
    )
    (net (code "76") (name "unconnected-(U$1-PadICSP4)") (class "Default")
      (node (ref "U$1") (pin "ICSP4") (pinfunction "ICSP4_ICSP4") (pintype "bidirectional"))
    )
    (net (code "77") (name "unconnected-(U$1-PadICSP5)") (class "Default")
      (node (ref "U$1") (pin "ICSP5") (pinfunction "ICSP5_ICSP5") (pintype "bidirectional"))
    )
    (net (code "78") (name "unconnected-(U$1-PadICSP6)") (class "Default")
      (node (ref "U$1") (pin "ICSP6") (pinfunction "ICSP6_ICSP6") (pintype "bidirectional"))
    )
    (net (code "79") (name "unconnected-(U$1-PadRAW)") (class "Default")
      (node (ref "U$1") (pin "RAW") (pinfunction "RAW_RAW") (pintype "bidirectional"))
    )
    (net (code "80") (name "unconnected-(U$1-PadRST)") (class "Default")
      (node (ref "U$1") (pin "RST") (pinfunction "RST_RST") (pintype "bidirectional"))
    )
    (net (code "81") (name "unconnected-(U$1-PadRST1)") (class "Default")
      (node (ref "U$1") (pin "RST1") (pinfunction "RST1_RST1") (pintype "bidirectional"))
    )
    (net (code "82") (name "unconnected-(U$1-PadRX1)") (class "Default")
      (node (ref "U$1") (pin "RX1") (pinfunction "RX1_RX1") (pintype "bidirectional"))
    )
    (net (code "83") (name "unconnected-(U$1-PadTX0)") (class "Default")
      (node (ref "U$1") (pin "TX0") (pinfunction "TX0_TX0") (pintype "bidirectional"))
    )
    (net (code "84") (name "unconnected-(U1-D2-Pad8)") (class "Default")
      (node (ref "U1") (pin "8") (pinfunction "D2_8") (pintype "bidirectional"))
    )
    (net (code "85") (name "unconnected-(U1-D3-Pad10)") (class "Default")
      (node (ref "U1") (pin "10") (pinfunction "D3_10") (pintype "bidirectional"))
    )
    (net (code "86") (name "unconnected-(U1-D4-Pad12)") (class "Default")
      (node (ref "U1") (pin "12") (pinfunction "D4_12") (pintype "bidirectional"))
    )
    (net (code "87") (name "unconnected-(U1-D5-Pad13)") (class "Default")
      (node (ref "U1") (pin "13") (pinfunction "D5_13") (pintype "bidirectional"))
    )
    (net (code "88") (name "unconnected-(U1-D6-Pad15)") (class "Default")
      (node (ref "U1") (pin "15") (pinfunction "D6_15") (pintype "bidirectional"))
    )
    (net (code "89") (name "unconnected-(U1-D7-Pad17)") (class "Default")
      (node (ref "U1") (pin "17") (pinfunction "D7_17") (pintype "bidirectional"))
    )
    (net (code "90") (name "unconnected-(U1-D8-Pad19)") (class "Default")
      (node (ref "U1") (pin "19") (pinfunction "D8_19") (pintype "bidirectional"))
    )
    (net (code "91") (name "unconnected-(U1-DOUT-Pad22)") (class "Default")
      (node (ref "U1") (pin "22") (pinfunction "DOUT_22") (pintype "output"))
    )
  )
)
